# Audio_Output_XLR1.net
KiCad netlist of a schematic drawn in Altium Designer
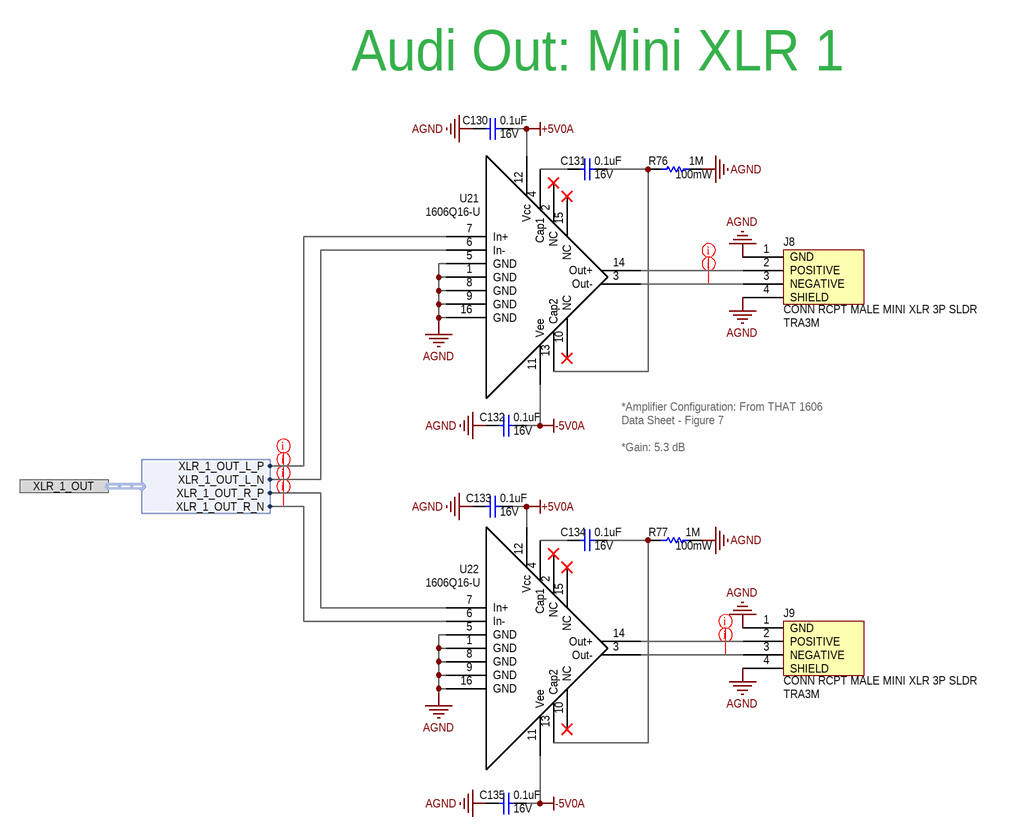
[diagram p0: Audio_Output_XLR1.SchDoc]

(export (version "E")
  (design (tool "Eeschema 10.0.6"))
  (components
    (comp (ref "C130")
      (value "CL10F104ZO8NNNC")
      (footprint "3-0603_L")
      (description "CAP CER 0.1UF 16V Y5V 0603")
      (fields
        (field (name "MANUFACTURER") "Samsung")
        (field (name "TOLERANCE") "80%")
        (field (name "VOLTAGE RATING") "16V")
        (field (name "CAPACITANCE") "0.1uF")
      )
      (libsource (lib "Schematic_Components_CD") (part "CL10F104ZO8NNNC"))
    )
    (comp (ref "C131")
      (value "CL10F104ZO8NNNC")
      (footprint "3-0603_L")
      (description "CAP CER 0.1UF 16V Y5V 0603")
      (fields
        (field (name "MANUFACTURER") "Samsung")
        (field (name "TOLERANCE") "80%")
        (field (name "VOLTAGE RATING") "16V")
        (field (name "CAPACITANCE") "0.1uF")
      )
      (libsource (lib "Schematic_Components_CD") (part "CL10F104ZO8NNNC"))
    )
    (comp (ref "C132")
      (value "CL10F104ZO8NNNC")
      (footprint "3-0603_L")
      (description "CAP CER 0.1UF 16V Y5V 0603")
      (fields
        (field (name "MANUFACTURER") "Samsung")
        (field (name "TOLERANCE") "80%")
        (field (name "VOLTAGE RATING") "16V")
        (field (name "CAPACITANCE") "0.1uF")
      )
      (libsource (lib "Schematic_Components_CD") (part "CL10F104ZO8NNNC"))
    )
    (comp (ref "C133")
      (value "CL10F104ZO8NNNC")
      (footprint "3-0603_L")
      (description "CAP CER 0.1UF 16V Y5V 0603")
      (fields
        (field (name "MANUFACTURER") "Samsung")
        (field (name "TOLERANCE") "80%")
        (field (name "VOLTAGE RATING") "16V")
        (field (name "CAPACITANCE") "0.1uF")
      )
      (libsource (lib "Schematic_Components_CD") (part "CL10F104ZO8NNNC"))
    )
    (comp (ref "C134")
      (value "CL10F104ZO8NNNC")
      (footprint "3-0603_L")
      (description "CAP CER 0.1UF 16V Y5V 0603")
      (fields
        (field (name "MANUFACTURER") "Samsung")
        (field (name "TOLERANCE") "80%")
        (field (name "VOLTAGE RATING") "16V")
        (field (name "CAPACITANCE") "0.1uF")
      )
      (libsource (lib "Schematic_Components_CD") (part "CL10F104ZO8NNNC"))
    )
    (comp (ref "C135")
      (value "CL10F104ZO8NNNC")
      (footprint "3-0603_L")
      (description "CAP CER 0.1UF 16V Y5V 0603")
      (fields
        (field (name "MANUFACTURER") "Samsung")
        (field (name "TOLERANCE") "80%")
        (field (name "VOLTAGE RATING") "16V")
        (field (name "CAPACITANCE") "0.1uF")
      )
      (libsource (lib "Schematic_Components_CD") (part "CL10F104ZO8NNNC"))
    )
    (comp (ref "J8")
      (value "CONN RCPT MALE MINI XLR 3P SLDR")
      (footprint "TRA3M")
      (description "3 Position Circular Connector Receptacle, Male Pins Solder Silver")
      (fields (field (name "MANUFACTURER") "Switchcraft") (field (name "MANUFACTURER PART NUMBER") "TRA3M"))
      (libsource (lib "Schematic_Components_CD") (part "TRA3M"))
    )
    (comp (ref "J9")
      (value "CONN RCPT MALE MINI XLR 3P SLDR")
      (footprint "TRA3M")
      (description "3 Position Circular Connector Receptacle, Male Pins Solder Silver")
      (fields (field (name "MANUFACTURER") "Switchcraft") (field (name "MANUFACTURER PART NUMBER") "TRA3M"))
      (libsource (lib "Schematic_Components_CD") (part "TRA3M"))
    )
    (comp (ref "R76")
      (value "RMCF0603FG1M00")
      (footprint "3-0603_R_L")
      (description "RES 1M OHM 1% 1/10W 0603")
      (fields
        (field (name "MANUFACTURER") "Stackpole Electronics")
        (field (name "TOLERANCE") "1%")
        (field (name "MAX POWER DISSIPATION") "100mW")
        (field (name "RESISTANCE") "1M")
      )
      (libsource (lib "Schematic_Components_CD") (part "RMCF0603FG1M00"))
    )
    (comp (ref "R77")
      (value "RMCF0603FG1M00")
      (footprint "3-0603_R_L")
      (description "RES 1M OHM 1% 1/10W 0603")
      (fields
        (field (name "MANUFACTURER") "Stackpole Electronics")
        (field (name "TOLERANCE") "1%")
        (field (name "MAX POWER DISSIPATION") "100mW")
        (field (name "RESISTANCE") "1M")
      )
      (libsource (lib "Schematic_Components_CD") (part "RMCF0603FG1M00"))
    )
    (comp (ref "U21")
      (value "1606Q16-U")
      (footprint "SOP64P600X175-16N")
      (description "Audio Amplifiers Balanced Audio Line Driver IC")
      (fields (field (name "MANUFACTURER") "THAT") (field (name "MANUFACTURER PART NUMBER") "1606Q16-U"))
      (libsource (lib "Schematic_Components_CD") (part "1606Q16-U"))
    )
    (comp (ref "U22")
      (value "1606Q16-U")
      (footprint "SOP64P600X175-16N")
      (description "Audio Amplifiers Balanced Audio Line Driver IC")
      (fields (field (name "MANUFACTURER") "THAT") (field (name "MANUFACTURER PART NUMBER") "1606Q16-U"))
      (libsource (lib "Schematic_Components_CD") (part "1606Q16-U"))
    )
  )
  (nets
    (net (code "2") (name "+5V0A") (class "Default")
      (node (ref "C130") (pin "1") (pinfunction "1_1") (pintype "passive"))
      (node (ref "C133") (pin "1") (pinfunction "1_1") (pintype "passive"))
      (node (ref "U21") (pin "12") (pinfunction "Vcc_12") (pintype "passive"))
      (node (ref "U22") (pin "12") (pinfunction "Vcc_12") (pintype "passive"))
    )
    (net (code "3") (name "-5V0A") (class "Default")
      (node (ref "C132") (pin "1") (pinfunction "1_1") (pintype "passive"))
      (node (ref "C135") (pin "1") (pinfunction "1_1") (pintype "passive"))
      (node (ref "U21") (pin "11") (pinfunction "Vee_11") (pintype "passive"))
      (node (ref "U22") (pin "11") (pinfunction "Vee_11") (pintype "passive"))
    )
    (net (code "4") (name "/XLR_1_OUT_L_N") (class "Default")
      (node (ref "U21") (pin "6") (pinfunction "In-_6") (pintype "passive"))
    )
    (net (code "5") (name "/XLR_1_OUT_L_P") (class "Default")
      (node (ref "U21") (pin "7") (pinfunction "In+_7") (pintype "passive"))
    )
    (net (code "6") (name "/XLR_1_OUT_R_N") (class "Default")
      (node (ref "U22") (pin "6") (pinfunction "In-_6") (pintype "passive"))
    )
    (net (code "7") (name "/XLR_1_OUT_R_P") (class "Default")
      (node (ref "U22") (pin "7") (pinfunction "In+_7") (pintype "passive"))
    )
    (net (code "9") (name "AGND") (class "Default")
      (node (ref "C130") (pin "2") (pinfunction "2_2") (pintype "passive"))
      (node (ref "C132") (pin "2") (pinfunction "2_2") (pintype "passive"))
      (node (ref "C133") (pin "2") (pinfunction "2_2") (pintype "passive"))
      (node (ref "C135") (pin "2") (pinfunction "2_2") (pintype "passive"))
      (node (ref "J8") (pin "1") (pinfunction "GND_1") (pintype "passive"))
      (node (ref "J8") (pin "4") (pinfunction "SHIELD_4") (pintype "passive"))
      (node (ref "J9") (pin "1") (pinfunction "GND_1") (pintype "passive"))
      (node (ref "J9") (pin "4") (pinfunction "SHIELD_4") (pintype "passive"))
      (node (ref "R76") (pin "2") (pinfunction "2_2") (pintype "passive"))
      (node (ref "R77") (pin "2") (pinfunction "2_2") (pintype "passive"))
      (node (ref "U21") (pin "1") (pinfunction "GND_1") (pintype "passive"))
      (node (ref "U21") (pin "16") (pinfunction "GND_16") (pintype "passive"))
      (node (ref "U21") (pin "5") (pinfunction "GND_5") (pintype "passive"))
      (node (ref "U21") (pin "8") (pinfunction "GND_8") (pintype "passive"))
      (node (ref "U21") (pin "9") (pinfunction "GND_9") (pintype "passive"))
      (node (ref "U22") (pin "1") (pinfunction "GND_1") (pintype "passive"))
      (node (ref "U22") (pin "16") (pinfunction "GND_16") (pintype "passive"))
      (node (ref "U22") (pin "5") (pinfunction "GND_5") (pintype "passive"))
      (node (ref "U22") (pin "8") (pinfunction "GND_8") (pintype "passive"))
      (node (ref "U22") (pin "9") (pinfunction "GND_9") (pintype "passive"))
    )
    (net (code "10") (name "Net-(J8-NEGATIVE)") (class "Default")
      (node (ref "J8") (pin "3") (pinfunction "NEGATIVE_3") (pintype "passive"))
      (node (ref "U21") (pin "3") (pinfunction "Out-_3") (pintype "passive"))
    )
    (net (code "11") (name "Net-(J8-POSITIVE)") (class "Default")
      (node (ref "J8") (pin "2") (pinfunction "POSITIVE_2") (pintype "passive"))
      (node (ref "U21") (pin "14") (pinfunction "Out+_14") (pintype "passive"))
    )
    (net (code "12") (name "Net-(J9-NEGATIVE)") (class "Default")
      (node (ref "J9") (pin "3") (pinfunction "NEGATIVE_3") (pintype "passive"))
      (node (ref "U22") (pin "3") (pinfunction "Out-_3") (pintype "passive"))
    )
    (net (code "13") (name "Net-(J9-POSITIVE)") (class "Default")
      (node (ref "J9") (pin "2") (pinfunction "POSITIVE_2") (pintype "passive"))
      (node (ref "U22") (pin "14") (pinfunction "Out+_14") (pintype "passive"))
    )
    (net (code "14") (name "Net-(U21-Cap1)") (class "Default")
      (node (ref "C131") (pin "2") (pinfunction "2_2") (pintype "passive"))
      (node (ref "U21") (pin "4") (pinfunction "Cap1_4") (pintype "passive"))
    )
    (net (code "15") (name "Net-(U21-Cap2)") (class "Default")
      (node (ref "C131") (pin "1") (pinfunction "1_1") (pintype "passive"))
      (node (ref "R76") (pin "1") (pinfunction "1_1") (pintype "passive"))
      (node (ref "U21") (pin "13") (pinfunction "Cap2_13") (pintype "passive"))
    )
    (net (code "16") (name "Net-(U22-Cap1)") (class "Default")
      (node (ref "C134") (pin "2") (pinfunction "2_2") (pintype "passive"))
      (node (ref "U22") (pin "4") (pinfunction "Cap1_4") (pintype "passive"))
    )
    (net (code "17") (name "Net-(U22-Cap2)") (class "Default")
      (node (ref "C134") (pin "1") (pinfunction "1_1") (pintype "passive"))
      (node (ref "R77") (pin "1") (pinfunction "1_1") (pintype "passive"))
      (node (ref "U22") (pin "13") (pinfunction "Cap2_13") (pintype "passive"))
    )
    (net (code "18") (name "unconnected-(U21-NC-Pad2)") (class "Default")
      (node (ref "U21") (pin "2") (pinfunction "NC_2") (pintype "passive+no_connect"))
    )
    (net (code "19") (name "unconnected-(U21-NC-Pad10)") (class "Default")
      (node (ref "U21") (pin "10") (pinfunction "NC_10") (pintype "passive+no_connect"))
    )
    (net (code "20") (name "unconnected-(U21-NC-Pad15)") (class "Default")
      (node (ref "U21") (pin "15") (pinfunction "NC_15") (pintype "passive+no_connect"))
    )
    (net (code "21") (name "unconnected-(U22-NC-Pad2)") (class "Default")
      (node (ref "U22") (pin "2") (pinfunction "NC_2") (pintype "passive+no_connect"))
    )
    (net (code "22") (name "unconnected-(U22-NC-Pad10)") (class "Default")
      (node (ref "U22") (pin "10") (pinfunction "NC_10") (pintype "passive+no_connect"))
    )
    (net (code "23") (name "unconnected-(U22-NC-Pad15)") (class "Default")
      (node (ref "U22") (pin "15") (pinfunction "NC_15") (pintype "passive+no_connect"))
    )
  )
)
